# oresat-card.net
KiCad netlist of a schematic drawn in EAGLE
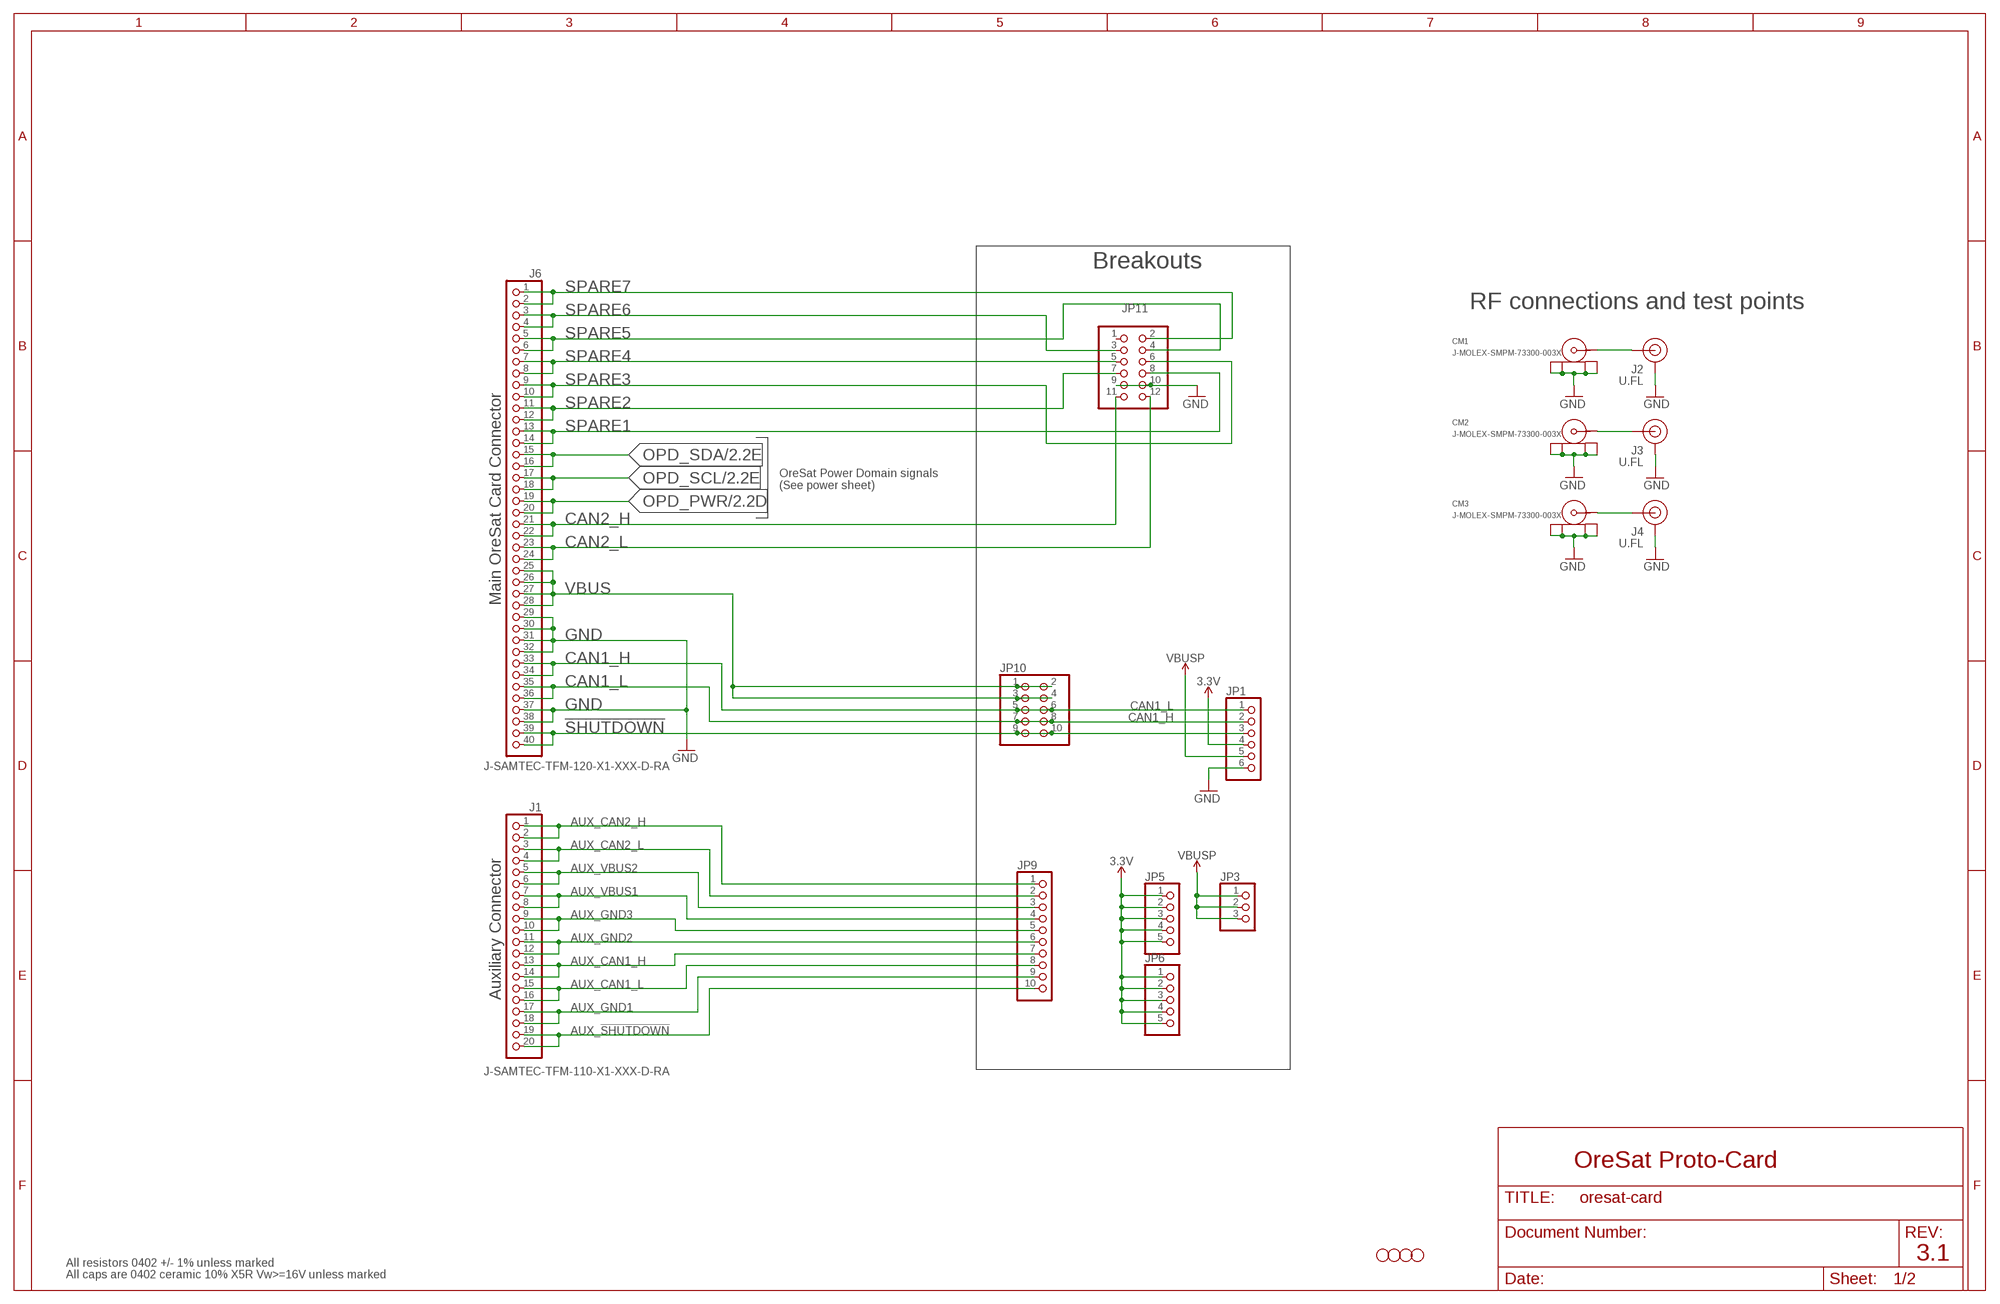
[diagram p0: schematic, sheet 1]
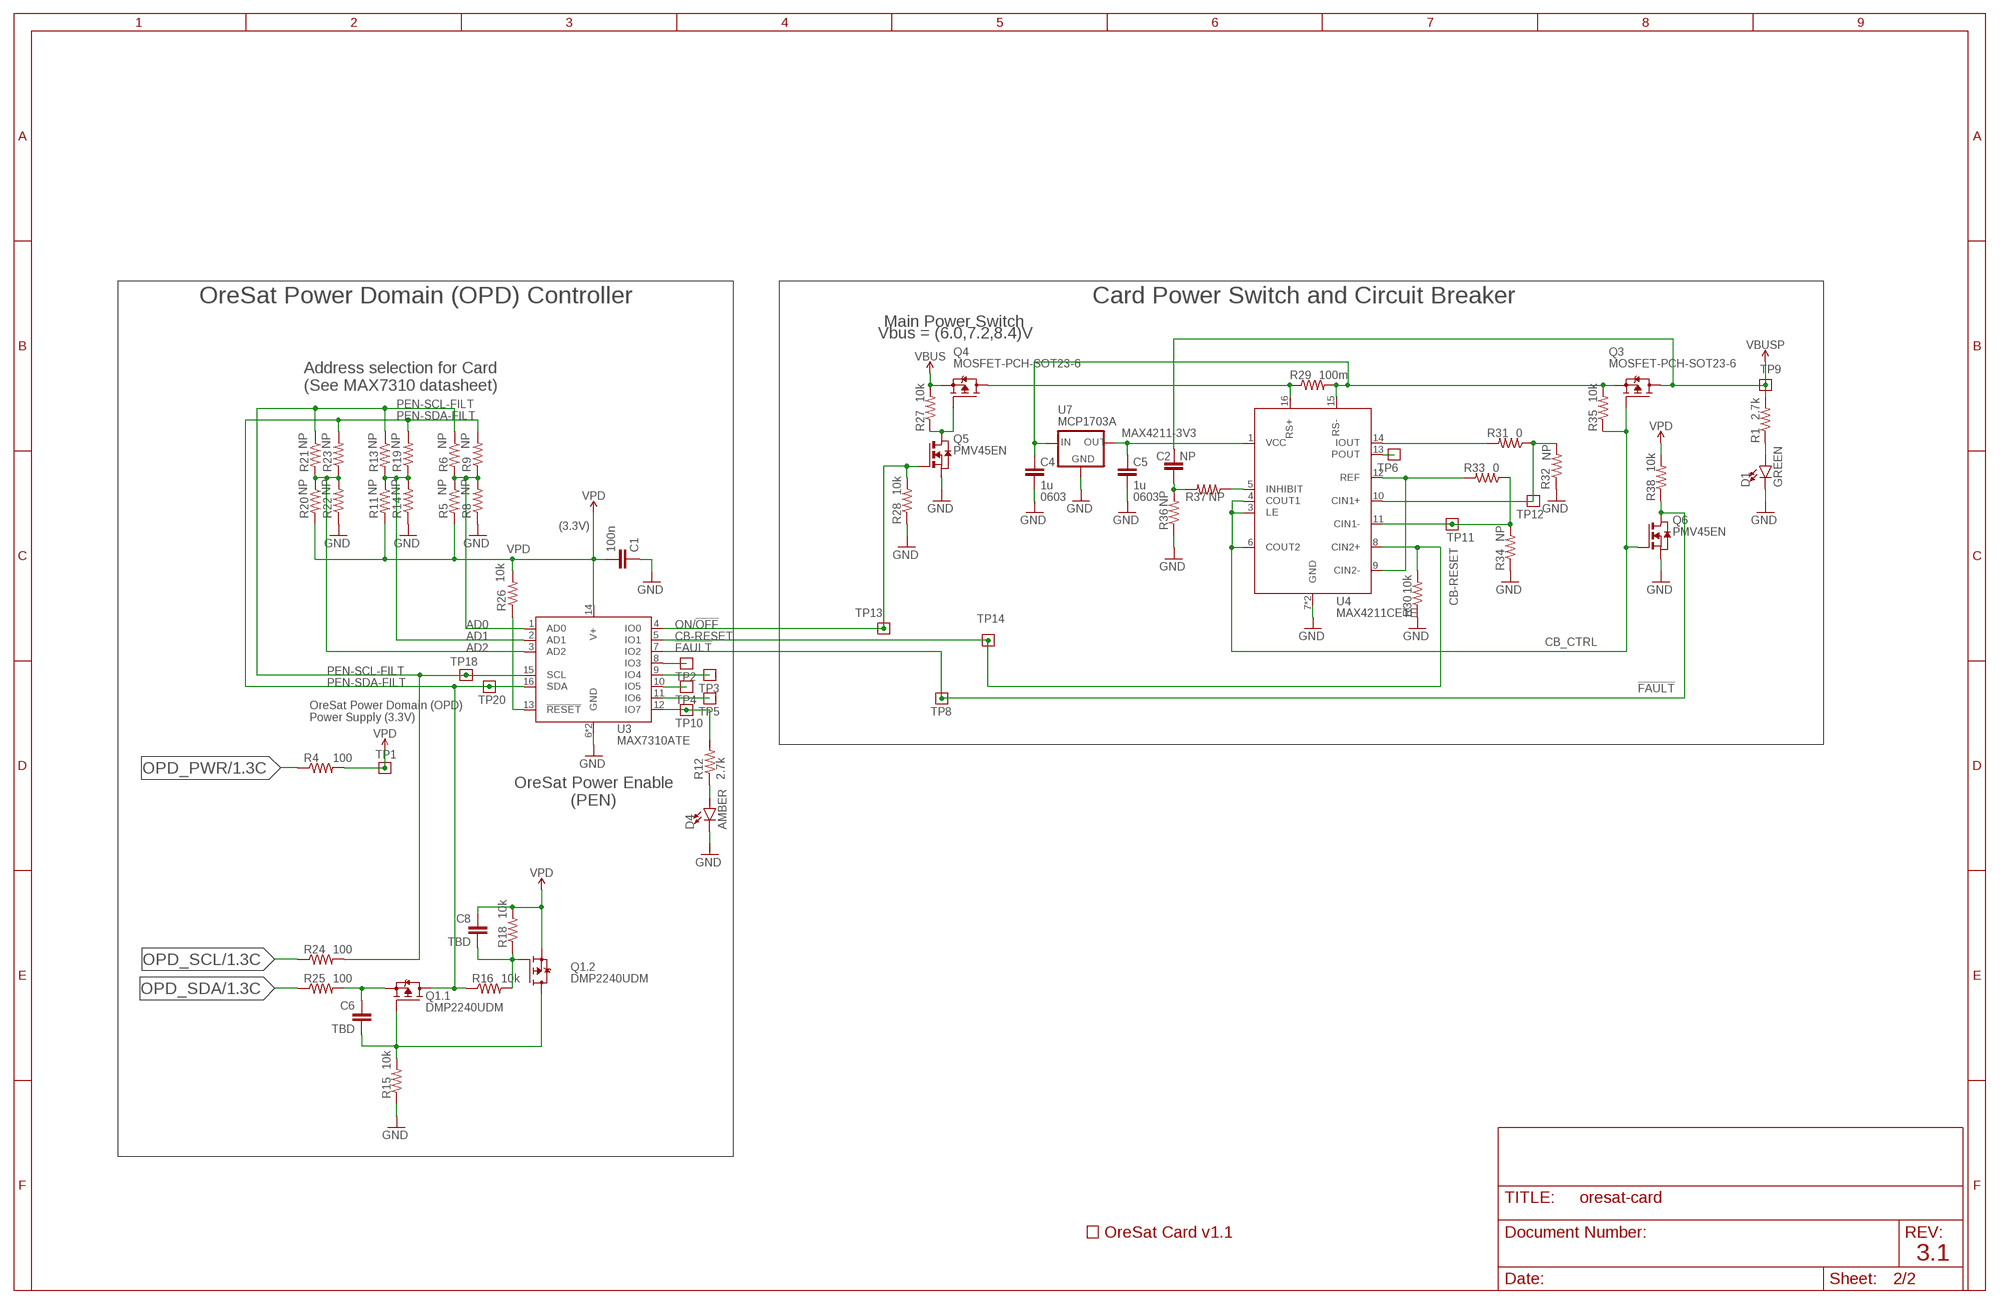
[diagram p1: schematic, sheet 2]

(export (version "E")
  (design (tool "Eeschema 10.0.6"))
  (components
    (comp (ref "C1")
      (value "100n")
      (footprint "eagle-import:.0402-B-NOSILK")
      (fields (field (name "MFR") "Samsung") (field (name "MPN") "CL05B104KO5NNNC"))
      (libsource (lib "eagle-import") (part "rcl_custom_C-EU0402-B-NOSILK"))
    )
    (comp (ref "C2")
      (value "NP")
      (footprint "eagle-import:.0402-B-NOSILK")
      (fields (field (name "MFR") "Samsung") (field (name "MPN") "CL05B104KO5NNNC"))
      (libsource (lib "eagle-import") (part "rcl_custom_C-EU0402-B-NOSILK"))
    )
    (comp (ref "C4")
      (value "1u")
      (footprint "eagle-import:.0603-B-NOSILK")
      (fields (field (name "MFR") "Samsung") (field (name "MPN") "CL05B104KO5NNNC"))
      (libsource (lib "eagle-import") (part "C-EU0603-B-NOSILK"))
    )
    (comp (ref "C5")
      (value "1u")
      (footprint "eagle-import:.0603-B-NOSILK")
      (fields (field (name "MFR") "Samsung") (field (name "MPN") "CL05B104KO5NNNC"))
      (libsource (lib "eagle-import") (part "C-EU0603-B-NOSILK"))
    )
    (comp (ref "C6")
      (value "TBD")
      (footprint "eagle-import:.0402-B-NOSILK")
      (fields (field (name "MFR") "Samsung") (field (name "MPN") "CL05B104KO5NNNC"))
      (libsource (lib "eagle-import") (part "rcl_custom_C-EU0402-B-NOSILK"))
    )
    (comp (ref "C8")
      (value "TBD")
      (footprint "eagle-import:.0402-B-NOSILK")
      (fields (field (name "MFR") "Samsung") (field (name "MPN") "CL05B104KO5NNNC"))
      (libsource (lib "eagle-import") (part "rcl_custom_C-EU0402-B-NOSILK"))
    )
    (comp (ref "D1")
      (value "GREEN")
      (footprint "eagle-import:LED-0603")
      (libsource (lib "eagle-import") (part "LED-GREEN0603"))
    )
    (comp (ref "D4")
      (value "AMBER")
      (footprint "eagle-import:LED-0603")
      (libsource (lib "eagle-import") (part "LED-GREEN0603"))
    )
    (comp (ref "Q1")
      (value "DMP2240UDM")
      (footprint "eagle-import:SOT23-6")
      (fields (field (name "MFR") "Diodes Inc") (field (name "MPN") "DMP2240UDM"))
      (libsource (lib "eagle-import") (part "Q-MOSFET-PCH-dual-SOT23-6_MOSFET-PCH-SOT23-6"))
    )
    (comp (ref "Q3")
      (value "MOSFET-PCH-SOT23-6")
      (footprint "eagle-import:SOT23-6")
      (fields (field (name "MFR") "Diodes Inc") (field (name "MPN") "DMP3050LVT-7"))
      (libsource (lib "eagle-import") (part "MOSFET-PCH-SOT23-6"))
    )
    (comp (ref "Q4")
      (value "MOSFET-PCH-SOT23-6")
      (footprint "eagle-import:SOT23-6")
      (fields (field (name "MFR") "Diodes Inc") (field (name "MPN") "DMP3050LVT-7"))
      (libsource (lib "eagle-import") (part "MOSFET-PCH-SOT23-6"))
    )
    (comp (ref "Q5")
      (value "PMV45EN")
      (footprint "eagle-import:SOT23")
      (libsource (lib "eagle-import") (part "PMV45EN"))
    )
    (comp (ref "Q6")
      (value "PMV45EN")
      (footprint "eagle-import:SOT23")
      (libsource (lib "eagle-import") (part "PMV45EN"))
    )
    (comp (ref "R1")
      (value "2.7k")
      (footprint "eagle-import:.0402-B-NOSILK")
      (fields (field (name "MFR") "Samsung") (field (name "MPN") "RC1005F6653CS"))
      (libsource (lib "eagle-import") (part "R-US_0402-B-NOSILK"))
    )
    (comp (ref "R4")
      (value "100")
      (footprint "eagle-import:.0402-B-NOSILK")
      (fields (field (name "MFR") "Samsung") (field (name "MPN") "RC1005F6653CS"))
      (libsource (lib "eagle-import") (part "R-US_0402-B-NOSILK"))
    )
    (comp (ref "R5")
      (value "NP")
      (footprint "eagle-import:.0402-B-NOSILK")
      (fields (field (name "MFR") "Samsung") (field (name "MPN") "RC1005F6653CS"))
      (libsource (lib "eagle-import") (part "R-US_0402-B-NOSILK"))
    )
    (comp (ref "R6")
      (value "NP")
      (footprint "eagle-import:.0402-B-NOSILK")
      (fields (field (name "MFR") "Samsung") (field (name "MPN") "RC1005F6653CS"))
      (libsource (lib "eagle-import") (part "R-US_0402-B-NOSILK"))
    )
    (comp (ref "R8")
      (value "NP")
      (footprint "eagle-import:.0402-B-NOSILK")
      (fields (field (name "MFR") "Samsung") (field (name "MPN") "RC1005F6653CS"))
      (libsource (lib "eagle-import") (part "R-US_0402-B-NOSILK"))
    )
    (comp (ref "R9")
      (value "NP")
      (footprint "eagle-import:.0402-B-NOSILK")
      (fields (field (name "MFR") "Samsung") (field (name "MPN") "RC1005F6653CS"))
      (libsource (lib "eagle-import") (part "R-US_0402-B-NOSILK"))
    )
    (comp (ref "R11")
      (value "NP")
      (footprint "eagle-import:.0402-B-NOSILK")
      (fields (field (name "MFR") "Samsung") (field (name "MPN") "RC1005F6653CS"))
      (libsource (lib "eagle-import") (part "R-US_0402-B-NOSILK"))
    )
    (comp (ref "R12")
      (value "2.7k")
      (footprint "eagle-import:.0402-B-NOSILK")
      (fields (field (name "MFR") "Samsung") (field (name "MPN") "RC1005F6653CS"))
      (libsource (lib "eagle-import") (part "R-US_0402-B-NOSILK"))
    )
    (comp (ref "R13")
      (value "NP")
      (footprint "eagle-import:.0402-B-NOSILK")
      (fields (field (name "MFR") "Samsung") (field (name "MPN") "RC1005F6653CS"))
      (libsource (lib "eagle-import") (part "R-US_0402-B-NOSILK"))
    )
    (comp (ref "R14")
      (value "NP")
      (footprint "eagle-import:.0402-B-NOSILK")
      (fields (field (name "MFR") "Samsung") (field (name "MPN") "RC1005F6653CS"))
      (libsource (lib "eagle-import") (part "R-US_0402-B-NOSILK"))
    )
    (comp (ref "R15")
      (value "10k")
      (footprint "eagle-import:.0402-B-NOSILK")
      (fields (field (name "MFR") "Samsung") (field (name "MPN") "RC1005F6653CS"))
      (libsource (lib "eagle-import") (part "R-US_0402-B-NOSILK"))
    )
    (comp (ref "R16")
      (value "10k")
      (footprint "eagle-import:.0402-B-NOSILK")
      (fields (field (name "MFR") "Samsung") (field (name "MPN") "RC1005F6653CS"))
      (libsource (lib "eagle-import") (part "R-US_0402-B-NOSILK"))
    )
    (comp (ref "R18")
      (value "10k")
      (footprint "eagle-import:.0402-B-NOSILK")
      (fields (field (name "MFR") "Samsung") (field (name "MPN") "RC1005F6653CS"))
      (libsource (lib "eagle-import") (part "R-US_0402-B-NOSILK"))
    )
    (comp (ref "R19")
      (value "NP")
      (footprint "eagle-import:.0402-B-NOSILK")
      (fields (field (name "MFR") "Samsung") (field (name "MPN") "RC1005F6653CS"))
      (libsource (lib "eagle-import") (part "R-US_0402-B-NOSILK"))
    )
    (comp (ref "R20")
      (value "NP")
      (footprint "eagle-import:.0402-B-NOSILK")
      (fields (field (name "MFR") "Samsung") (field (name "MPN") "RC1005F6653CS"))
      (libsource (lib "eagle-import") (part "R-US_0402-B-NOSILK"))
    )
    (comp (ref "R21")
      (value "NP")
      (footprint "eagle-import:.0402-B-NOSILK")
      (fields (field (name "MFR") "Samsung") (field (name "MPN") "RC1005F6653CS"))
      (libsource (lib "eagle-import") (part "R-US_0402-B-NOSILK"))
    )
    (comp (ref "R22")
      (value "NP")
      (footprint "eagle-import:.0402-B-NOSILK")
      (fields (field (name "MFR") "Samsung") (field (name "MPN") "RC1005F6653CS"))
      (libsource (lib "eagle-import") (part "R-US_0402-B-NOSILK"))
    )
    (comp (ref "R23")
      (value "NP")
      (footprint "eagle-import:.0402-B-NOSILK")
      (fields (field (name "MFR") "Samsung") (field (name "MPN") "RC1005F6653CS"))
      (libsource (lib "eagle-import") (part "R-US_0402-B-NOSILK"))
    )
    (comp (ref "R24")
      (value "100")
      (footprint "eagle-import:.0402-B-NOSILK")
      (fields (field (name "MFR") "Samsung") (field (name "MPN") "RC1005F6653CS"))
      (libsource (lib "eagle-import") (part "R-US_0402-B-NOSILK"))
    )
    (comp (ref "R25")
      (value "100")
      (footprint "eagle-import:.0402-B-NOSILK")
      (fields (field (name "MFR") "Samsung") (field (name "MPN") "RC1005F6653CS"))
      (libsource (lib "eagle-import") (part "R-US_0402-B-NOSILK"))
    )
    (comp (ref "R26")
      (value "10k")
      (footprint "eagle-import:.0402-B-NOSILK")
      (fields (field (name "MFR") "Samsung") (field (name "MPN") "RC1005F6653CS"))
      (libsource (lib "eagle-import") (part "R-US_0402-B-NOSILK"))
    )
    (comp (ref "R27")
      (value "10k")
      (footprint "eagle-import:.0402-B-NOSILK")
      (fields (field (name "MFR") "Samsung") (field (name "MPN") "RC1005F6653CS"))
      (libsource (lib "eagle-import") (part "R-US_0402-B-NOSILK"))
    )
    (comp (ref "R28")
      (value "10k")
      (footprint "eagle-import:.0402-B-NOSILK")
      (fields (field (name "MFR") "Samsung") (field (name "MPN") "RC1005F6653CS"))
      (libsource (lib "eagle-import") (part "R-US_0402-B-NOSILK"))
    )
    (comp (ref "R29")
      (value "100m")
      (footprint "eagle-import:R1206")
      (libsource (lib "eagle-import") (part "R-US_R1206"))
    )
    (comp (ref "R30")
      (value "10k")
      (footprint "eagle-import:.0402-B-NOSILK")
      (fields (field (name "MFR") "Samsung") (field (name "MPN") "RC1005F6653CS"))
      (libsource (lib "eagle-import") (part "R-US_0402-B-NOSILK"))
    )
    (comp (ref "R31")
      (value "0")
      (footprint "eagle-import:.0402-B-NOSILK")
      (fields (field (name "MFR") "Samsung") (field (name "MPN") "RC1005F6653CS"))
      (libsource (lib "eagle-import") (part "R-US_0402-B-NOSILK"))
    )
    (comp (ref "R32")
      (value "NP")
      (footprint "eagle-import:.0402-B-NOSILK")
      (fields (field (name "MFR") "Samsung") (field (name "MPN") "RC1005F6653CS"))
      (libsource (lib "eagle-import") (part "R-US_0402-B-NOSILK"))
    )
    (comp (ref "R33")
      (value "0")
      (footprint "eagle-import:.0402-B-NOSILK")
      (fields (field (name "MFR") "Samsung") (field (name "MPN") "RC1005F6653CS"))
      (libsource (lib "eagle-import") (part "R-US_0402-B-NOSILK"))
    )
    (comp (ref "R34")
      (value "NP")
      (footprint "eagle-import:.0402-B-NOSILK")
      (fields (field (name "MFR") "Samsung") (field (name "MPN") "RC1005F6653CS"))
      (libsource (lib "eagle-import") (part "R-US_0402-B-NOSILK"))
    )
    (comp (ref "R35")
      (value "10k")
      (footprint "eagle-import:.0402-B-NOSILK")
      (fields (field (name "MFR") "Samsung") (field (name "MPN") "RC1005F6653CS"))
      (libsource (lib "eagle-import") (part "R-US_0402-B-NOSILK"))
    )
    (comp (ref "R36")
      (value "NP")
      (footprint "eagle-import:.0402-B-NOSILK")
      (fields (field (name "MFR") "Samsung") (field (name "MPN") "RC1005F6653CS"))
      (libsource (lib "eagle-import") (part "R-US_0402-B-NOSILK"))
    )
    (comp (ref "R37")
      (value "NP")
      (footprint "eagle-import:.0402-B-NOSILK")
      (fields (field (name "MFR") "Samsung") (field (name "MPN") "RC1005F6653CS"))
      (libsource (lib "eagle-import") (part "R-US_0402-B-NOSILK"))
    )
    (comp (ref "R38")
      (value "10k")
      (footprint "eagle-import:.0402-B-NOSILK")
      (fields (field (name "MFR") "Samsung") (field (name "MPN") "RC1005F6653CS"))
      (libsource (lib "eagle-import") (part "R-US_0402-B-NOSILK"))
    )
    (comp (ref "TP1")
      (value "TEST-POINT")
      (footprint "eagle-import:2MM-TEST-POINT")
      (libsource (lib "eagle-import") (part "TEST-POINT"))
    )
    (comp (ref "TP2")
      (value "TEST-POINT")
      (footprint "eagle-import:2MM-TEST-POINT")
      (libsource (lib "eagle-import") (part "TEST-POINT"))
    )
    (comp (ref "TP3")
      (value "TEST-POINT")
      (footprint "eagle-import:2MM-TEST-POINT")
      (libsource (lib "eagle-import") (part "TEST-POINT"))
    )
    (comp (ref "TP4")
      (value "TEST-POINT")
      (footprint "eagle-import:2MM-TEST-POINT")
      (libsource (lib "eagle-import") (part "TEST-POINT"))
    )
    (comp (ref "TP5")
      (value "TEST-POINT")
      (footprint "eagle-import:2MM-TEST-POINT")
      (libsource (lib "eagle-import") (part "TEST-POINT"))
    )
    (comp (ref "TP6")
      (value "TEST-POINT")
      (footprint "eagle-import:2MM-TEST-POINT")
      (libsource (lib "eagle-import") (part "TEST-POINT"))
    )
    (comp (ref "TP8")
      (value "TEST-POINT")
      (footprint "eagle-import:2MM-TEST-POINT")
      (libsource (lib "eagle-import") (part "TEST-POINT"))
    )
    (comp (ref "TP9")
      (value "TEST-POINT")
      (footprint "eagle-import:2MM-TEST-POINT")
      (libsource (lib "eagle-import") (part "TEST-POINT"))
    )
    (comp (ref "TP10")
      (value "TEST-POINT")
      (footprint "eagle-import:2MM-TEST-POINT")
      (libsource (lib "eagle-import") (part "TEST-POINT"))
    )
    (comp (ref "TP11")
      (value "TEST-POINT")
      (footprint "eagle-import:2MM-TEST-POINT")
      (libsource (lib "eagle-import") (part "TEST-POINT"))
    )
    (comp (ref "TP12")
      (value "TEST-POINT")
      (footprint "eagle-import:2MM-TEST-POINT")
      (libsource (lib "eagle-import") (part "TEST-POINT"))
    )
    (comp (ref "TP13")
      (value "TEST-POINT")
      (footprint "eagle-import:2MM-TEST-POINT")
      (libsource (lib "eagle-import") (part "TEST-POINT"))
    )
    (comp (ref "TP14")
      (value "TEST-POINT")
      (footprint "eagle-import:2MM-TEST-POINT")
      (libsource (lib "eagle-import") (part "TEST-POINT"))
    )
    (comp (ref "TP18")
      (value "TEST-POINT")
      (footprint "eagle-import:2MM-TEST-POINT")
      (libsource (lib "eagle-import") (part "TEST-POINT"))
    )
    (comp (ref "TP20")
      (value "TEST-POINT")
      (footprint "eagle-import:2MM-TEST-POINT")
      (libsource (lib "eagle-import") (part "TEST-POINT"))
    )
    (comp (ref "U$1")
      (value "ORESAT-CARD-V1.1-3XRF")
      (footprint "eagle-import:ORESAT-CARD-V1.1-3XRF")
      (libsource (lib "eagle-import") (part "ORESAT-CARD-V1.1-3XRF"))
    )
    (comp (ref "U3")
      (value "MAX7310ATE")
      (footprint "eagle-import:QFN65P400X400X80-17T210")
      (fields (field (name "MFR") "Maxim"))
      (libsource (lib "eagle-import") (part "MAX7310"))
    )
    (comp (ref "U4")
      (value "MAX4211CETE")
      (footprint "eagle-import:QFN65P400X400X80-17T210")
      (fields (field (name "MFR") "Maxim"))
      (libsource (lib "eagle-import") (part "MAX4211"))
    )
    (comp (ref "U7")
      (value "MCP1703A")
      (footprint "eagle-import:SOT23")
      (fields (field (name "MFR") "Microchip") (field (name "MPN") "MCP1703AT-3302E/CB"))
      (libsource (lib "eagle-import") (part "XC63FPM"))
    )
    (comp (ref "CM1")
      (value "J-MOLEX-SMPM-73300-003X")
      (footprint "eagle-import:J-MOLEX-SMPM-073300-003X")
      (fields (field (name "MFR") "Molex") (field (name "MPN") "73300-0020"))
      (libsource (lib "eagle-import") (part "J-MOLEX-SMPM-73300-003X"))
    )
    (comp (ref "CM2")
      (value "J-MOLEX-SMPM-73300-003X")
      (footprint "eagle-import:J-MOLEX-SMPM-073300-003X")
      (fields (field (name "MFR") "Molex") (field (name "MPN") "73300-0020"))
      (libsource (lib "eagle-import") (part "J-MOLEX-SMPM-73300-003X"))
    )
    (comp (ref "CM3")
      (value "J-MOLEX-SMPM-73300-003X")
      (footprint "eagle-import:J-MOLEX-SMPM-073300-003X")
      (fields (field (name "MFR") "Molex") (field (name "MPN") "73300-0020"))
      (libsource (lib "eagle-import") (part "J-MOLEX-SMPM-73300-003X"))
    )
    (comp (ref "H1")
      (value "STAND-OFFTIGHT")
      (footprint "eagle-import:STAND-OFF-TIGHT")
      (libsource (lib "eagle-import") (part "STAND-OFFTIGHT"))
    )
    (comp (ref "H2")
      (value "STAND-OFFTIGHT")
      (footprint "eagle-import:STAND-OFF-TIGHT")
      (libsource (lib "eagle-import") (part "STAND-OFFTIGHT"))
    )
    (comp (ref "H3")
      (value "STAND-OFFTIGHT")
      (footprint "eagle-import:STAND-OFF-TIGHT")
      (libsource (lib "eagle-import") (part "STAND-OFFTIGHT"))
    )
    (comp (ref "H4")
      (value "STAND-OFFTIGHT")
      (footprint "eagle-import:STAND-OFF-TIGHT")
      (libsource (lib "eagle-import") (part "STAND-OFFTIGHT"))
    )
    (comp (ref "J1")
      (value "J-SAMTEC-TFM-110-X1-XXX-D-RA")
      (footprint "eagle-import:J-SAMTEC-TFM-110-X1-XXX-D-RA")
      (fields (field (name "MFR") "Samtec") (field (name "MPN") "TFM-110-01-L-D-RA "))
      (libsource (lib "eagle-import") (part "J-SAMTEC-TFM-110-X1-XXX-D-RA"))
    )
    (comp (ref "J2")
      (value "U.FL")
      (footprint "eagle-import:U.FL")
      (libsource (lib "eagle-import") (part "U.FL2PIN"))
    )
    (comp (ref "J3")
      (value "U.FL")
      (footprint "eagle-import:U.FL")
      (libsource (lib "eagle-import") (part "U.FL2PIN"))
    )
    (comp (ref "J4")
      (value "U.FL")
      (footprint "eagle-import:U.FL")
      (libsource (lib "eagle-import") (part "U.FL2PIN"))
    )
    (comp (ref "J6")
      (value "J-SAMTEC-TFM-120-X1-XXX-D-RA")
      (footprint "eagle-import:J-SAMTEC-TFM-120-X1-XXX-D-RA")
      (fields (field (name "MFR") "Samtec") (field (name "MPN") "TFM-120-01-L-D-RA"))
      (libsource (lib "eagle-import") (part "J-SAMTEC-TFM-120-X1-XXX-D-RA"))
    )
    (comp (ref "JP1")
      (value "PINHD-1X6")
      (footprint "eagle-import:1X06")
      (libsource (lib "eagle-import") (part "PINHD-1X6"))
    )
    (comp (ref "JP3")
      (value "PINHD-1X3")
      (footprint "eagle-import:1X03")
      (libsource (lib "eagle-import") (part "PINHD-1X3"))
    )
    (comp (ref "JP5")
      (value "PINHD-1X5")
      (footprint "eagle-import:1X05")
      (libsource (lib "eagle-import") (part "PINHD-1X5"))
    )
    (comp (ref "JP6")
      (value "PINHD-1X5")
      (footprint "eagle-import:1X05")
      (libsource (lib "eagle-import") (part "PINHD-1X5"))
    )
    (comp (ref "JP9")
      (value "PINHD-1X10")
      (footprint "eagle-import:1X10")
      (libsource (lib "eagle-import") (part "PINHD-1X10"))
    )
    (comp (ref "JP10")
      (value "PINHD-2X5")
      (footprint "eagle-import:2X05")
      (libsource (lib "eagle-import") (part "PINHD-2X5"))
    )
    (comp (ref "JP11")
      (value "PINHD-2X6")
      (footprint "eagle-import:2X06")
      (libsource (lib "eagle-import") (part "PINHD-2X6"))
    )
  )
  (nets
    (net (code "1") (name "3.3V") (class "Default")
      (node (ref "JP1") (pin "4") (pinfunction "4_4") (pintype "passive"))
      (node (ref "JP5") (pin "1") (pinfunction "1_1") (pintype "passive"))
      (node (ref "JP5") (pin "2") (pinfunction "2_2") (pintype "passive"))
      (node (ref "JP5") (pin "3") (pinfunction "3_3") (pintype "passive"))
      (node (ref "JP5") (pin "4") (pinfunction "4_4") (pintype "passive"))
      (node (ref "JP5") (pin "5") (pinfunction "5_5") (pintype "passive"))
      (node (ref "JP6") (pin "1") (pinfunction "1_1") (pintype "passive"))
      (node (ref "JP6") (pin "2") (pinfunction "2_2") (pintype "passive"))
      (node (ref "JP6") (pin "3") (pinfunction "3_3") (pintype "passive"))
      (node (ref "JP6") (pin "4") (pinfunction "4_4") (pintype "passive"))
      (node (ref "JP6") (pin "5") (pinfunction "5_5") (pintype "passive"))
    )
    (net (code "2") (name "AD0") (class "Default")
      (node (ref "R5") (pin "1") (pinfunction "1_1") (pintype "passive"))
      (node (ref "R6") (pin "2") (pinfunction "2_2") (pintype "passive"))
      (node (ref "R8") (pin "2") (pinfunction "2_2") (pintype "passive"))
      (node (ref "R9") (pin "1") (pinfunction "1_1") (pintype "passive"))
      (node (ref "U3") (pin "1") (pinfunction "AD0_1") (pintype "input"))
    )
    (net (code "3") (name "AD1") (class "Default")
      (node (ref "R11") (pin "1") (pinfunction "1_1") (pintype "passive"))
      (node (ref "R13") (pin "2") (pinfunction "2_2") (pintype "passive"))
      (node (ref "R14") (pin "2") (pinfunction "2_2") (pintype "passive"))
      (node (ref "R19") (pin "1") (pinfunction "1_1") (pintype "passive"))
      (node (ref "U3") (pin "2") (pinfunction "AD1_2") (pintype "input"))
    )
    (net (code "4") (name "AD2") (class "Default")
      (node (ref "R20") (pin "1") (pinfunction "1_1") (pintype "passive"))
      (node (ref "R21") (pin "2") (pinfunction "2_2") (pintype "passive"))
      (node (ref "R22") (pin "2") (pinfunction "2_2") (pintype "passive"))
      (node (ref "R23") (pin "1") (pinfunction "1_1") (pintype "passive"))
      (node (ref "U3") (pin "3") (pinfunction "AD2_3") (pintype "input"))
    )
    (net (code "5") (name "AUX_CAN1_H") (class "Default")
      (node (ref "J1") (pin "13") (pinfunction "13_13") (pintype "passive"))
      (node (ref "J1") (pin "14") (pinfunction "14_14") (pintype "passive"))
      (node (ref "JP9") (pin "7") (pinfunction "7_7") (pintype "passive"))
    )
    (net (code "6") (name "AUX_CAN1_L") (class "Default")
      (node (ref "J1") (pin "15") (pinfunction "15_15") (pintype "passive"))
      (node (ref "J1") (pin "16") (pinfunction "16_16") (pintype "passive"))
      (node (ref "JP9") (pin "8") (pinfunction "8_8") (pintype "passive"))
    )
    (net (code "7") (name "AUX_CAN2_H") (class "Default")
      (node (ref "J1") (pin "1") (pinfunction "1_1") (pintype "passive"))
      (node (ref "J1") (pin "2") (pinfunction "2_2") (pintype "passive"))
      (node (ref "JP9") (pin "1") (pinfunction "1_1") (pintype "passive"))
    )
    (net (code "8") (name "AUX_CAN2_L") (class "Default")
      (node (ref "J1") (pin "3") (pinfunction "3_3") (pintype "passive"))
      (node (ref "J1") (pin "4") (pinfunction "4_4") (pintype "passive"))
      (node (ref "JP9") (pin "2") (pinfunction "2_2") (pintype "passive"))
    )
    (net (code "9") (name "AUX_GND1") (class "Default")
      (node (ref "J1") (pin "17") (pinfunction "17_17") (pintype "passive"))
      (node (ref "J1") (pin "18") (pinfunction "18_18") (pintype "passive"))
      (node (ref "JP9") (pin "9") (pinfunction "9_9") (pintype "passive"))
    )
    (net (code "10") (name "AUX_GND2") (class "Default")
      (node (ref "J1") (pin "11") (pinfunction "11_11") (pintype "passive"))
      (node (ref "J1") (pin "12") (pinfunction "12_12") (pintype "passive"))
      (node (ref "JP9") (pin "6") (pinfunction "6_6") (pintype "passive"))
    )
    (net (code "11") (name "AUX_GND3") (class "Default")
      (node (ref "J1") (pin "10") (pinfunction "10_10") (pintype "passive"))
      (node (ref "J1") (pin "9") (pinfunction "9_9") (pintype "passive"))
      (node (ref "JP9") (pin "5") (pinfunction "5_5") (pintype "passive"))
    )
    (net (code "12") (name "AUX_VBUS1") (class "Default")
      (node (ref "J1") (pin "7") (pinfunction "7_7") (pintype "passive"))
      (node (ref "J1") (pin "8") (pinfunction "8_8") (pintype "passive"))
      (node (ref "JP9") (pin "4") (pinfunction "4_4") (pintype "passive"))
    )
    (net (code "13") (name "AUX_VBUS2") (class "Default")
      (node (ref "J1") (pin "5") (pinfunction "5_5") (pintype "passive"))
      (node (ref "J1") (pin "6") (pinfunction "6_6") (pintype "passive"))
      (node (ref "JP9") (pin "3") (pinfunction "3_3") (pintype "passive"))
    )
    (net (code "14") (name "AUX_~{SHUTDOWN}") (class "Default")
      (node (ref "J1") (pin "19") (pinfunction "19_19") (pintype "passive"))
      (node (ref "J1") (pin "20") (pinfunction "20_20") (pintype "passive"))
      (node (ref "JP9") (pin "10") (pinfunction "10_10") (pintype "passive"))
    )
    (net (code "15") (name "CAN1_H") (class "Default")
      (node (ref "J6") (pin "33") (pinfunction "33_33") (pintype "passive"))
      (node (ref "J6") (pin "34") (pinfunction "34_34") (pintype "passive"))
      (node (ref "JP1") (pin "1") (pinfunction "1_1") (pintype "passive"))
      (node (ref "JP10") (pin "5") (pinfunction "5_5") (pintype "passive"))
      (node (ref "JP10") (pin "6") (pinfunction "6_6") (pintype "passive"))
    )
    (net (code "16") (name "CAN1_L") (class "Default")
      (node (ref "J6") (pin "35") (pinfunction "35_35") (pintype "passive"))
      (node (ref "J6") (pin "36") (pinfunction "36_36") (pintype "passive"))
      (node (ref "JP1") (pin "2") (pinfunction "2_2") (pintype "passive"))
      (node (ref "JP10") (pin "7") (pinfunction "7_7") (pintype "passive"))
      (node (ref "JP10") (pin "8") (pinfunction "8_8") (pintype "passive"))
    )
    (net (code "17") (name "CAN2_H") (class "Default")
      (node (ref "J6") (pin "21") (pinfunction "21_21") (pintype "passive"))
      (node (ref "J6") (pin "22") (pinfunction "22_22") (pintype "passive"))
      (node (ref "JP11") (pin "11") (pinfunction "11_11") (pintype "passive"))
    )
    (net (code "18") (name "CAN2_L") (class "Default")
      (node (ref "J6") (pin "23") (pinfunction "23_23") (pintype "passive"))
      (node (ref "J6") (pin "24") (pinfunction "24_24") (pintype "passive"))
      (node (ref "JP11") (pin "12") (pinfunction "12_12") (pintype "passive"))
    )
    (net (code "19") (name "CB-RESET") (class "Default")
      (node (ref "R30") (pin "2") (pinfunction "2_2") (pintype "passive"))
      (node (ref "TP14") (pin "1") (pinfunction "1_1") (pintype "passive"))
      (node (ref "U3") (pin "5") (pinfunction "IO1_5") (pintype "bidirectional"))
      (node (ref "U4") (pin "8") (pinfunction "CIN2+_8") (pintype "input"))
    )
    (net (code "20") (name "CB_CTRL") (class "Default")
      (node (ref "Q3") (pin "3") (pinfunction "G_3") (pintype "passive"))
      (node (ref "Q6") (pin "1") (pinfunction "G_1") (pintype "passive"))
      (node (ref "R35") (pin "1") (pinfunction "1_1") (pintype "passive"))
      (node (ref "U4") (pin "3") (pinfunction "LE_3") (pintype "input"))
      (node (ref "U4") (pin "4") (pinfunction "COUT1_4") (pintype "open_collector"))
      (node (ref "U4") (pin "6") (pinfunction "COUT2_6") (pintype "open_collector"))
    )
    (net (code "21") (name "GND") (class "Default")
      (node (ref "C1") (pin "1") (pinfunction "1_1") (pintype "passive"))
      (node (ref "C4") (pin "2") (pinfunction "2_2") (pintype "passive"))
      (node (ref "C5") (pin "2") (pinfunction "2_2") (pintype "passive"))
      (node (ref "CM1") (pin "P$1") (pinfunction "SHIELD3_P$1") (pintype "passive"))
      (node (ref "CM1") (pin "P$2") (pinfunction "SHIELD2_P$2") (pintype "passive"))
      (node (ref "CM1") (pin "P$3") (pinfunction "SHIELD1_P$3") (pintype "passive"))
      (node (ref "CM1") (pin "P$4") (pinfunction "SHIELD_P$4") (pintype "passive"))
      (node (ref "CM2") (pin "P$1") (pinfunction "SHIELD3_P$1") (pintype "passive"))
      (node (ref "CM2") (pin "P$2") (pinfunction "SHIELD2_P$2") (pintype "passive"))
      (node (ref "CM2") (pin "P$3") (pinfunction "SHIELD1_P$3") (pintype "passive"))
      (node (ref "CM2") (pin "P$4") (pinfunction "SHIELD_P$4") (pintype "passive"))
      (node (ref "CM3") (pin "P$1") (pinfunction "SHIELD3_P$1") (pintype "passive"))
      (node (ref "CM3") (pin "P$2") (pinfunction "SHIELD2_P$2") (pintype "passive"))
      (node (ref "CM3") (pin "P$3") (pinfunction "SHIELD1_P$3") (pintype "passive"))
      (node (ref "CM3") (pin "P$4") (pinfunction "SHIELD_P$4") (pintype "passive"))
      (node (ref "D1") (pin "C") (pinfunction "C_C") (pintype "passive"))
      (node (ref "D4") (pin "C") (pinfunction "C_C") (pintype "passive"))
      (node (ref "J2") (pin "1") (pinfunction "GND_1") (pintype "bidirectional"))
      (node (ref "J2") (pin "2") (pinfunction "GND_2") (pintype "bidirectional"))
      (node (ref "J3") (pin "1") (pinfunction "GND_1") (pintype "bidirectional"))
      (node (ref "J3") (pin "2") (pinfunction "GND_2") (pintype "bidirectional"))
      (node (ref "J4") (pin "1") (pinfunction "GND_1") (pintype "bidirectional"))
      (node (ref "J4") (pin "2") (pinfunction "GND_2") (pintype "bidirectional"))
      (node (ref "J6") (pin "29") (pinfunction "29_29") (pintype "passive"))
      (node (ref "J6") (pin "30") (pinfunction "30_30") (pintype "passive"))
      (node (ref "J6") (pin "31") (pinfunction "31_31") (pintype "passive"))
      (node (ref "J6") (pin "32") (pinfunction "32_32") (pintype "passive"))
      (node (ref "J6") (pin "37") (pinfunction "37_37") (pintype "passive"))
      (node (ref "J6") (pin "38") (pinfunction "38_38") (pintype "passive"))
      (node (ref "JP1") (pin "6") (pinfunction "6_6") (pintype "passive"))
      (node (ref "JP11") (pin "10") (pinfunction "10_10") (pintype "passive"))
      (node (ref "JP11") (pin "9") (pinfunction "9_9") (pintype "passive"))
      (node (ref "Q5") (pin "2") (pinfunction "S_2") (pintype "passive"))
      (node (ref "Q6") (pin "2") (pinfunction "S_2") (pintype "passive"))
      (node (ref "R14") (pin "1") (pinfunction "1_1") (pintype "passive"))
      (node (ref "R15") (pin "1") (pinfunction "1_1") (pintype "passive"))
      (node (ref "R22") (pin "1") (pinfunction "1_1") (pintype "passive"))
      (node (ref "R28") (pin "1") (pinfunction "1_1") (pintype "passive"))
      (node (ref "R30") (pin "1") (pinfunction "1_1") (pintype "passive"))
      (node (ref "R32") (pin "1") (pinfunction "1_1") (pintype "passive"))
      (node (ref "R34") (pin "1") (pinfunction "1_1") (pintype "passive"))
      (node (ref "R36") (pin "1") (pinfunction "1_1") (pintype "passive"))
      (node (ref "R8") (pin "1") (pinfunction "1_1") (pintype "passive"))
      (node (ref "U3") (pin "6") (pinfunction "GND_6") (pintype "power_in"))
      (node (ref "U3") (pin "EPAD") (pinfunction "GND_EPAD") (pintype "power_in"))
      (node (ref "U4") (pin "7") (pinfunction "GND_7") (pintype "power_in"))
      (node (ref "U4") (pin "EPAD") (pinfunction "GND_EPAD") (pintype "power_in"))
      (node (ref "U7") (pin "1") (pinfunction "GND_1") (pintype "input"))
    )
    (net (code "22") (name "MAX4211-3V3") (class "Default")
      (node (ref "C5") (pin "1") (pinfunction "1_1") (pintype "passive"))
      (node (ref "U4") (pin "1") (pinfunction "VCC_1") (pintype "power_in"))
      (node (ref "U7") (pin "2") (pinfunction "OUT_2") (pintype "passive"))
    )
    (net (code "23") (name "Net-(C2-Pad1)") (class "Default")
      (node (ref "C2") (pin "1") (pinfunction "1_1") (pintype "passive"))
      (node (ref "R36") (pin "2") (pinfunction "2_2") (pintype "passive"))
      (node (ref "R37") (pin "2") (pinfunction "2_2") (pintype "passive"))
    )
    (net (code "24") (name "Net-(CM1-CENTER)") (class "Default")
      (node (ref "CM1") (pin "RF") (pinfunction "CENTER_RF") (pintype "passive"))
      (node (ref "J2") (pin "FEED") (pinfunction "SIGNAL_FEED") (pintype "bidirectional"))
    )
    (net (code "25") (name "Net-(CM2-CENTER)") (class "Default")
      (node (ref "CM2") (pin "RF") (pinfunction "CENTER_RF") (pintype "passive"))
      (node (ref "J3") (pin "FEED") (pinfunction "SIGNAL_FEED") (pintype "bidirectional"))
    )
    (net (code "26") (name "Net-(CM3-CENTER)") (class "Default")
      (node (ref "CM3") (pin "RF") (pinfunction "CENTER_RF") (pintype "passive"))
      (node (ref "J4") (pin "FEED") (pinfunction "SIGNAL_FEED") (pintype "bidirectional"))
    )
    (net (code "27") (name "Net-(D1-PadA)") (class "Default")
      (node (ref "D1") (pin "A") (pinfunction "A_A") (pintype "passive"))
      (node (ref "R1") (pin "1") (pinfunction "1_1") (pintype "passive"))
    )
    (net (code "28") (name "Net-(D4-PadA)") (class "Default")
      (node (ref "D4") (pin "A") (pinfunction "A_A") (pintype "passive"))
      (node (ref "R12") (pin "1") (pinfunction "1_1") (pintype "passive"))
    )
    (net (code "29") (name "Net-(Q1A-G)") (class "Default")
      (node (ref "C6") (pin "2") (pinfunction "2_2") (pintype "passive"))
      (node (ref "Q1") (pin "1") (pinfunction "G_1") (pintype "passive"))
      (node (ref "Q1") (pin "4") (pinfunction "D_4") (pintype "passive"))
      (node (ref "R15") (pin "2") (pinfunction "2_2") (pintype "passive"))
    )
    (net (code "30") (name "Net-(Q1A-S)") (class "Default")
      (node (ref "C6") (pin "1") (pinfunction "1_1") (pintype "passive"))
      (node (ref "Q1") (pin "5") (pinfunction "S_5") (pintype "passive"))
      (node (ref "R25") (pin "2") (pinfunction "2_2") (pintype "passive"))
    )
    (net (code "31") (name "Net-(Q1B-G)") (class "Default")
      (node (ref "C8") (pin "2") (pinfunction "2_2") (pintype "passive"))
      (node (ref "Q1") (pin "3") (pinfunction "G_3") (pintype "passive"))
      (node (ref "R16") (pin "2") (pinfunction "2_2") (pintype "passive"))
      (node (ref "R18") (pin "1") (pinfunction "1_1") (pintype "passive"))
    )
    (net (code "32") (name "Net-(Q3-S)") (class "Default")
      (node (ref "C4") (pin "1") (pinfunction "1_1") (pintype "passive"))
      (node (ref "Q3") (pin "4") (pinfunction "S_4") (pintype "passive"))
      (node (ref "R29") (pin "2") (pinfunction "2_2") (pintype "passive"))
      (node (ref "R35") (pin "2") (pinfunction "2_2") (pintype "passive"))
      (node (ref "U4") (pin "15") (pinfunction "RS-_15") (pintype "passive"))
      (node (ref "U7") (pin "3") (pinfunction "IN_3") (pintype "input"))
    )
    (net (code "33") (name "Net-(Q4-G)") (class "Default")
      (node (ref "Q4") (pin "3") (pinfunction "G_3") (pintype "passive"))
      (node (ref "Q5") (pin "3") (pinfunction "D_3") (pintype "passive"))
      (node (ref "R27") (pin "1") (pinfunction "1_1") (pintype "passive"))
    )
    (net (code "34") (name "Net-(U3-IO3)") (class "Default")
      (node (ref "TP2") (pin "1") (pinfunction "1_1") (pintype "passive"))
      (node (ref "U3") (pin "8") (pinfunction "IO3_8") (pintype "bidirectional"))
    )
    (net (code "35") (name "Net-(U3-IO4)") (class "Default")
      (node (ref "TP3") (pin "1") (pinfunction "1_1") (pintype "passive"))
      (node (ref "U3") (pin "9") (pinfunction "IO4_9") (pintype "bidirectional"))
    )
    (net (code "36") (name "Net-(U3-IO5)") (class "Default")
      (node (ref "TP4") (pin "1") (pinfunction "1_1") (pintype "passive"))
      (node (ref "U3") (pin "10") (pinfunction "IO5_10") (pintype "bidirectional"))
    )
    (net (code "37") (name "Net-(U3-IO6)") (class "Default")
      (node (ref "TP5") (pin "1") (pinfunction "1_1") (pintype "passive"))
      (node (ref "U3") (pin "11") (pinfunction "IO6_11") (pintype "bidirectional"))
    )
    (net (code "38") (name "Net-(U3-IO7)") (class "Default")
      (node (ref "R12") (pin "2") (pinfunction "2_2") (pintype "passive"))
      (node (ref "TP10") (pin "1") (pinfunction "1_1") (pintype "passive"))
      (node (ref "U3") (pin "12") (pinfunction "IO7_12") (pintype "bidirectional"))
    )
    (net (code "39") (name "Net-(U3-~{RESET})") (class "Default")
      (node (ref "R26") (pin "1") (pinfunction "1_1") (pintype "passive"))
      (node (ref "U3") (pin "13") (pinfunction "~{RESET}_13") (pintype "input"))
    )
    (net (code "40") (name "Net-(U4-CIN1+)") (class "Default")
      (node (ref "R31") (pin "1") (pinfunction "1_1") (pintype "passive"))
      (node (ref "R32") (pin "2") (pinfunction "2_2") (pintype "passive"))
      (node (ref "TP12") (pin "1") (pinfunction "1_1") (pintype "passive"))
      (node (ref "U4") (pin "10") (pinfunction "CIN1+_10") (pintype "input"))
    )
    (net (code "41") (name "Net-(U4-CIN1-)") (class "Default")
      (node (ref "R33") (pin "1") (pinfunction "1_1") (pintype "passive"))
      (node (ref "R34") (pin "2") (pinfunction "2_2") (pintype "passive"))
      (node (ref "TP11") (pin "1") (pinfunction "1_1") (pintype "passive"))
      (node (ref "U4") (pin "11") (pinfunction "CIN1-_11") (pintype "input"))
    )
    (net (code "42") (name "Net-(U4-CIN2-)") (class "Default")
      (node (ref "R33") (pin "2") (pinfunction "2_2") (pintype "passive"))
      (node (ref "U4") (pin "12") (pinfunction "REF_12") (pintype "output"))
      (node (ref "U4") (pin "9") (pinfunction "CIN2-_9") (pintype "input"))
    )
    (net (code "43") (name "Net-(U4-INHIBIT)") (class "Default")
      (node (ref "R37") (pin "1") (pinfunction "1_1") (pintype "passive"))
      (node (ref "U4") (pin "5") (pinfunction "INHIBIT_5") (pintype "input"))
    )
    (net (code "44") (name "Net-(U4-IOUT)") (class "Default")
      (node (ref "R31") (pin "2") (pinfunction "2_2") (pintype "passive"))
      (node (ref "U4") (pin "14") (pinfunction "IOUT_14") (pintype "output"))
    )
    (net (code "45") (name "Net-(U4-POUT)") (class "Default")
      (node (ref "TP6") (pin "1") (pinfunction "1_1") (pintype "passive"))
      (node (ref "U4") (pin "13") (pinfunction "POUT_13") (pintype "output"))
    )
    (net (code "46") (name "Net-(U4-RS+)") (class "Default")
      (node (ref "Q4") (pin "1") (pinfunction "D_1") (pintype "passive"))
      (node (ref "Q4") (pin "2") (pinfunction "D_2") (pintype "passive"))
      (node (ref "Q4") (pin "5") (pinfunction "D_5") (pintype "passive"))
      (node (ref "Q4") (pin "6") (pinfunction "D_6") (pintype "passive"))
      (node (ref "R29") (pin "1") (pinfunction "1_1") (pintype "passive"))
      (node (ref "U4") (pin "16") (pinfunction "RS+_16") (pintype "passive"))
    )
    (net (code "47") (name "ON{slash}~{OFF}") (class "Default")
      (node (ref "Q5") (pin "1") (pinfunction "G_1") (pintype "passive"))
      (node (ref "R28") (pin "2") (pinfunction "2_2") (pintype "passive"))
      (node (ref "TP13") (pin "1") (pinfunction "1_1") (pintype "passive"))
      (node (ref "U3") (pin "4") (pinfunction "IO0_4") (pintype "bidirectional"))
    )
    (net (code "48") (name "OPD_PWR") (class "Default")
      (node (ref "J6") (pin "19") (pinfunction "19_19") (pintype "passive"))
      (node (ref "J6") (pin "20") (pinfunction "20_20") (pintype "passive"))
      (node (ref "R4") (pin "1") (pinfunction "1_1") (pintype "passive"))
    )
    (net (code "49") (name "OPD_SCL") (class "Default")
      (node (ref "J6") (pin "17") (pinfunction "17_17") (pintype "passive"))
      (node (ref "J6") (pin "18") (pinfunction "18_18") (pintype "passive"))
      (node (ref "R24") (pin "1") (pinfunction "1_1") (pintype "passive"))
    )
    (net (code "50") (name "OPD_SDA") (class "Default")
      (node (ref "J6") (pin "15") (pinfunction "15_15") (pintype "passive"))
      (node (ref "J6") (pin "16") (pinfunction "16_16") (pintype "passive"))
      (node (ref "R25") (pin "1") (pinfunction "1_1") (pintype "passive"))
    )
    (net (code "51") (name "PEN-SCL-FILT") (class "Default")
      (node (ref "R13") (pin "1") (pinfunction "1_1") (pintype "passive"))
      (node (ref "R21") (pin "1") (pinfunction "1_1") (pintype "passive"))
      (node (ref "R24") (pin "2") (pinfunction "2_2") (pintype "passive"))
      (node (ref "R6") (pin "1") (pinfunction "1_1") (pintype "passive"))
      (node (ref "TP18") (pin "1") (pinfunction "1_1") (pintype "passive"))
      (node (ref "U3") (pin "15") (pinfunction "SCL_15") (pintype "input"))
    )
    (net (code "52") (name "PEN-SDA-FILT") (class "Default")
      (node (ref "Q1") (pin "6") (pinfunction "D_6") (pintype "passive"))
      (node (ref "R16") (pin "1") (pinfunction "1_1") (pintype "passive"))
      (node (ref "R19") (pin "2") (pinfunction "2_2") (pintype "passive"))
      (node (ref "R23") (pin "2") (pinfunction "2_2") (pintype "passive"))
      (node (ref "R9") (pin "2") (pinfunction "2_2") (pintype "passive"))
      (node (ref "TP20") (pin "1") (pinfunction "1_1") (pintype "passive"))
      (node (ref "U3") (pin "16") (pinfunction "SDA_16") (pintype "bidirectional"))
    )
    (net (code "53") (name "SPARE1") (class "Default")
      (node (ref "J6") (pin "13") (pinfunction "13_13") (pintype "passive"))
      (node (ref "J6") (pin "14") (pinfunction "14_14") (pintype "passive"))
      (node (ref "JP11") (pin "8") (pinfunction "8_8") (pintype "passive"))
    )
    (net (code "54") (name "SPARE2") (class "Default")
      (node (ref "J6") (pin "11") (pinfunction "11_11") (pintype "passive"))
      (node (ref "J6") (pin "12") (pinfunction "12_12") (pintype "passive"))
      (node (ref "JP11") (pin "7") (pinfunction "7_7") (pintype "passive"))
    )
    (net (code "55") (name "SPARE3") (class "Default")
      (node (ref "J6") (pin "10") (pinfunction "10_10") (pintype "passive"))
      (node (ref "J6") (pin "9") (pinfunction "9_9") (pintype "passive"))
      (node (ref "JP11") (pin "6") (pinfunction "6_6") (pintype "passive"))
    )
    (net (code "56") (name "SPARE4") (class "Default")
      (node (ref "J6") (pin "7") (pinfunction "7_7") (pintype "passive"))
      (node (ref "J6") (pin "8") (pinfunction "8_8") (pintype "passive"))
      (node (ref "JP11") (pin "5") (pinfunction "5_5") (pintype "passive"))
    )
    (net (code "57") (name "SPARE5") (class "Default")
      (node (ref "J6") (pin "5") (pinfunction "5_5") (pintype "passive"))
      (node (ref "J6") (pin "6") (pinfunction "6_6") (pintype "passive"))
      (node (ref "JP11") (pin "4") (pinfunction "4_4") (pintype "passive"))
    )
    (net (code "58") (name "SPARE6") (class "Default")
      (node (ref "J6") (pin "3") (pinfunction "3_3") (pintype "passive"))
      (node (ref "J6") (pin "4") (pinfunction "4_4") (pintype "passive"))
      (node (ref "JP11") (pin "3") (pinfunction "3_3") (pintype "passive"))
    )
    (net (code "59") (name "SPARE7") (class "Default")
      (node (ref "J6") (pin "1") (pinfunction "1_1") (pintype "passive"))
      (node (ref "J6") (pin "2") (pinfunction "2_2") (pintype "passive"))
      (node (ref "JP11") (pin "2") (pinfunction "2_2") (pintype "passive"))
    )
    (net (code "60") (name "VBUS") (class "Default")
      (node (ref "J6") (pin "25") (pinfunction "25_25") (pintype "passive"))
      (node (ref "J6") (pin "26") (pinfunction "26_26") (pintype "passive"))
      (node (ref "J6") (pin "27") (pinfunction "27_27") (pintype "passive"))
      (node (ref "J6") (pin "28") (pinfunction "28_28") (pintype "passive"))
      (node (ref "JP10") (pin "1") (pinfunction "1_1") (pintype "passive"))
      (node (ref "JP10") (pin "2") (pinfunction "2_2") (pintype "passive"))
      (node (ref "JP10") (pin "3") (pinfunction "3_3") (pintype "passive"))
      (node (ref "JP10") (pin "4") (pinfunction "4_4") (pintype "passive"))
      (node (ref "Q4") (pin "4") (pinfunction "S_4") (pintype "passive"))
      (node (ref "R27") (pin "2") (pinfunction "2_2") (pintype "passive"))
    )
    (net (code "61") (name "VBUSP") (class "Default")
      (node (ref "C2") (pin "2") (pinfunction "2_2") (pintype "passive"))
      (node (ref "JP1") (pin "5") (pinfunction "5_5") (pintype "passive"))
      (node (ref "JP3") (pin "1") (pinfunction "1_1") (pintype "passive"))
      (node (ref "JP3") (pin "2") (pinfunction "2_2") (pintype "passive"))
      (node (ref "JP3") (pin "3") (pinfunction "3_3") (pintype "passive"))
      (node (ref "Q3") (pin "1") (pinfunction "D_1") (pintype "passive"))
      (node (ref "Q3") (pin "2") (pinfunction "D_2") (pintype "passive"))
      (node (ref "Q3") (pin "5") (pinfunction "D_5") (pintype "passive"))
      (node (ref "Q3") (pin "6") (pinfunction "D_6") (pintype "passive"))
      (node (ref "R1") (pin "2") (pinfunction "2_2") (pintype "passive"))
      (node (ref "TP9") (pin "1") (pinfunction "1_1") (pintype "passive"))
    )
    (net (code "62") (name "VPD") (class "Default")
      (node (ref "C1") (pin "2") (pinfunction "2_2") (pintype "passive"))
      (node (ref "C8") (pin "1") (pinfunction "1_1") (pintype "passive"))
      (node (ref "Q1") (pin "2") (pinfunction "S_2") (pintype "passive"))
      (node (ref "R11") (pin "2") (pinfunction "2_2") (pintype "passive"))
      (node (ref "R18") (pin "2") (pinfunction "2_2") (pintype "passive"))
      (node (ref "R20") (pin "2") (pinfunction "2_2") (pintype "passive"))
      (node (ref "R26") (pin "2") (pinfunction "2_2") (pintype "passive"))
      (node (ref "R38") (pin "2") (pinfunction "2_2") (pintype "passive"))
      (node (ref "R4") (pin "2") (pinfunction "2_2") (pintype "passive"))
      (node (ref "R5") (pin "2") (pinfunction "2_2") (pintype "passive"))
      (node (ref "TP1") (pin "1") (pinfunction "1_1") (pintype "passive"))
      (node (ref "U3") (pin "14") (pinfunction "V+_14") (pintype "power_in"))
    )
    (net (code "63") (name "unconnected-(JP11-Pad1)") (class "Default")
      (node (ref "JP11") (pin "1") (pinfunction "1_1") (pintype "passive"))
    )
    (net (code "64") (name "~{FAULT}") (class "Default")
      (node (ref "Q6") (pin "3") (pinfunction "D_3") (pintype "passive"))
      (node (ref "R38") (pin "1") (pinfunction "1_1") (pintype "passive"))
      (node (ref "TP8") (pin "1") (pinfunction "1_1") (pintype "passive"))
      (node (ref "U3") (pin "7") (pinfunction "IO2_7") (pintype "bidirectional"))
    )
    (net (code "65") (name "~{SHUTDOWN}") (class "Default")
      (node (ref "J6") (pin "39") (pinfunction "39_39") (pintype "passive"))
      (node (ref "J6") (pin "40") (pinfunction "40_40") (pintype "passive"))
      (node (ref "JP1") (pin "3") (pinfunction "3_3") (pintype "passive"))
      (node (ref "JP10") (pin "10") (pinfunction "10_10") (pintype "passive"))
      (node (ref "JP10") (pin "9") (pinfunction "9_9") (pintype "passive"))
    )
  )
)
